# SCH_Light-Meter-Schematic_2025-04-22_1.net
KiCad netlist of a schematic drawn in EasyEDA
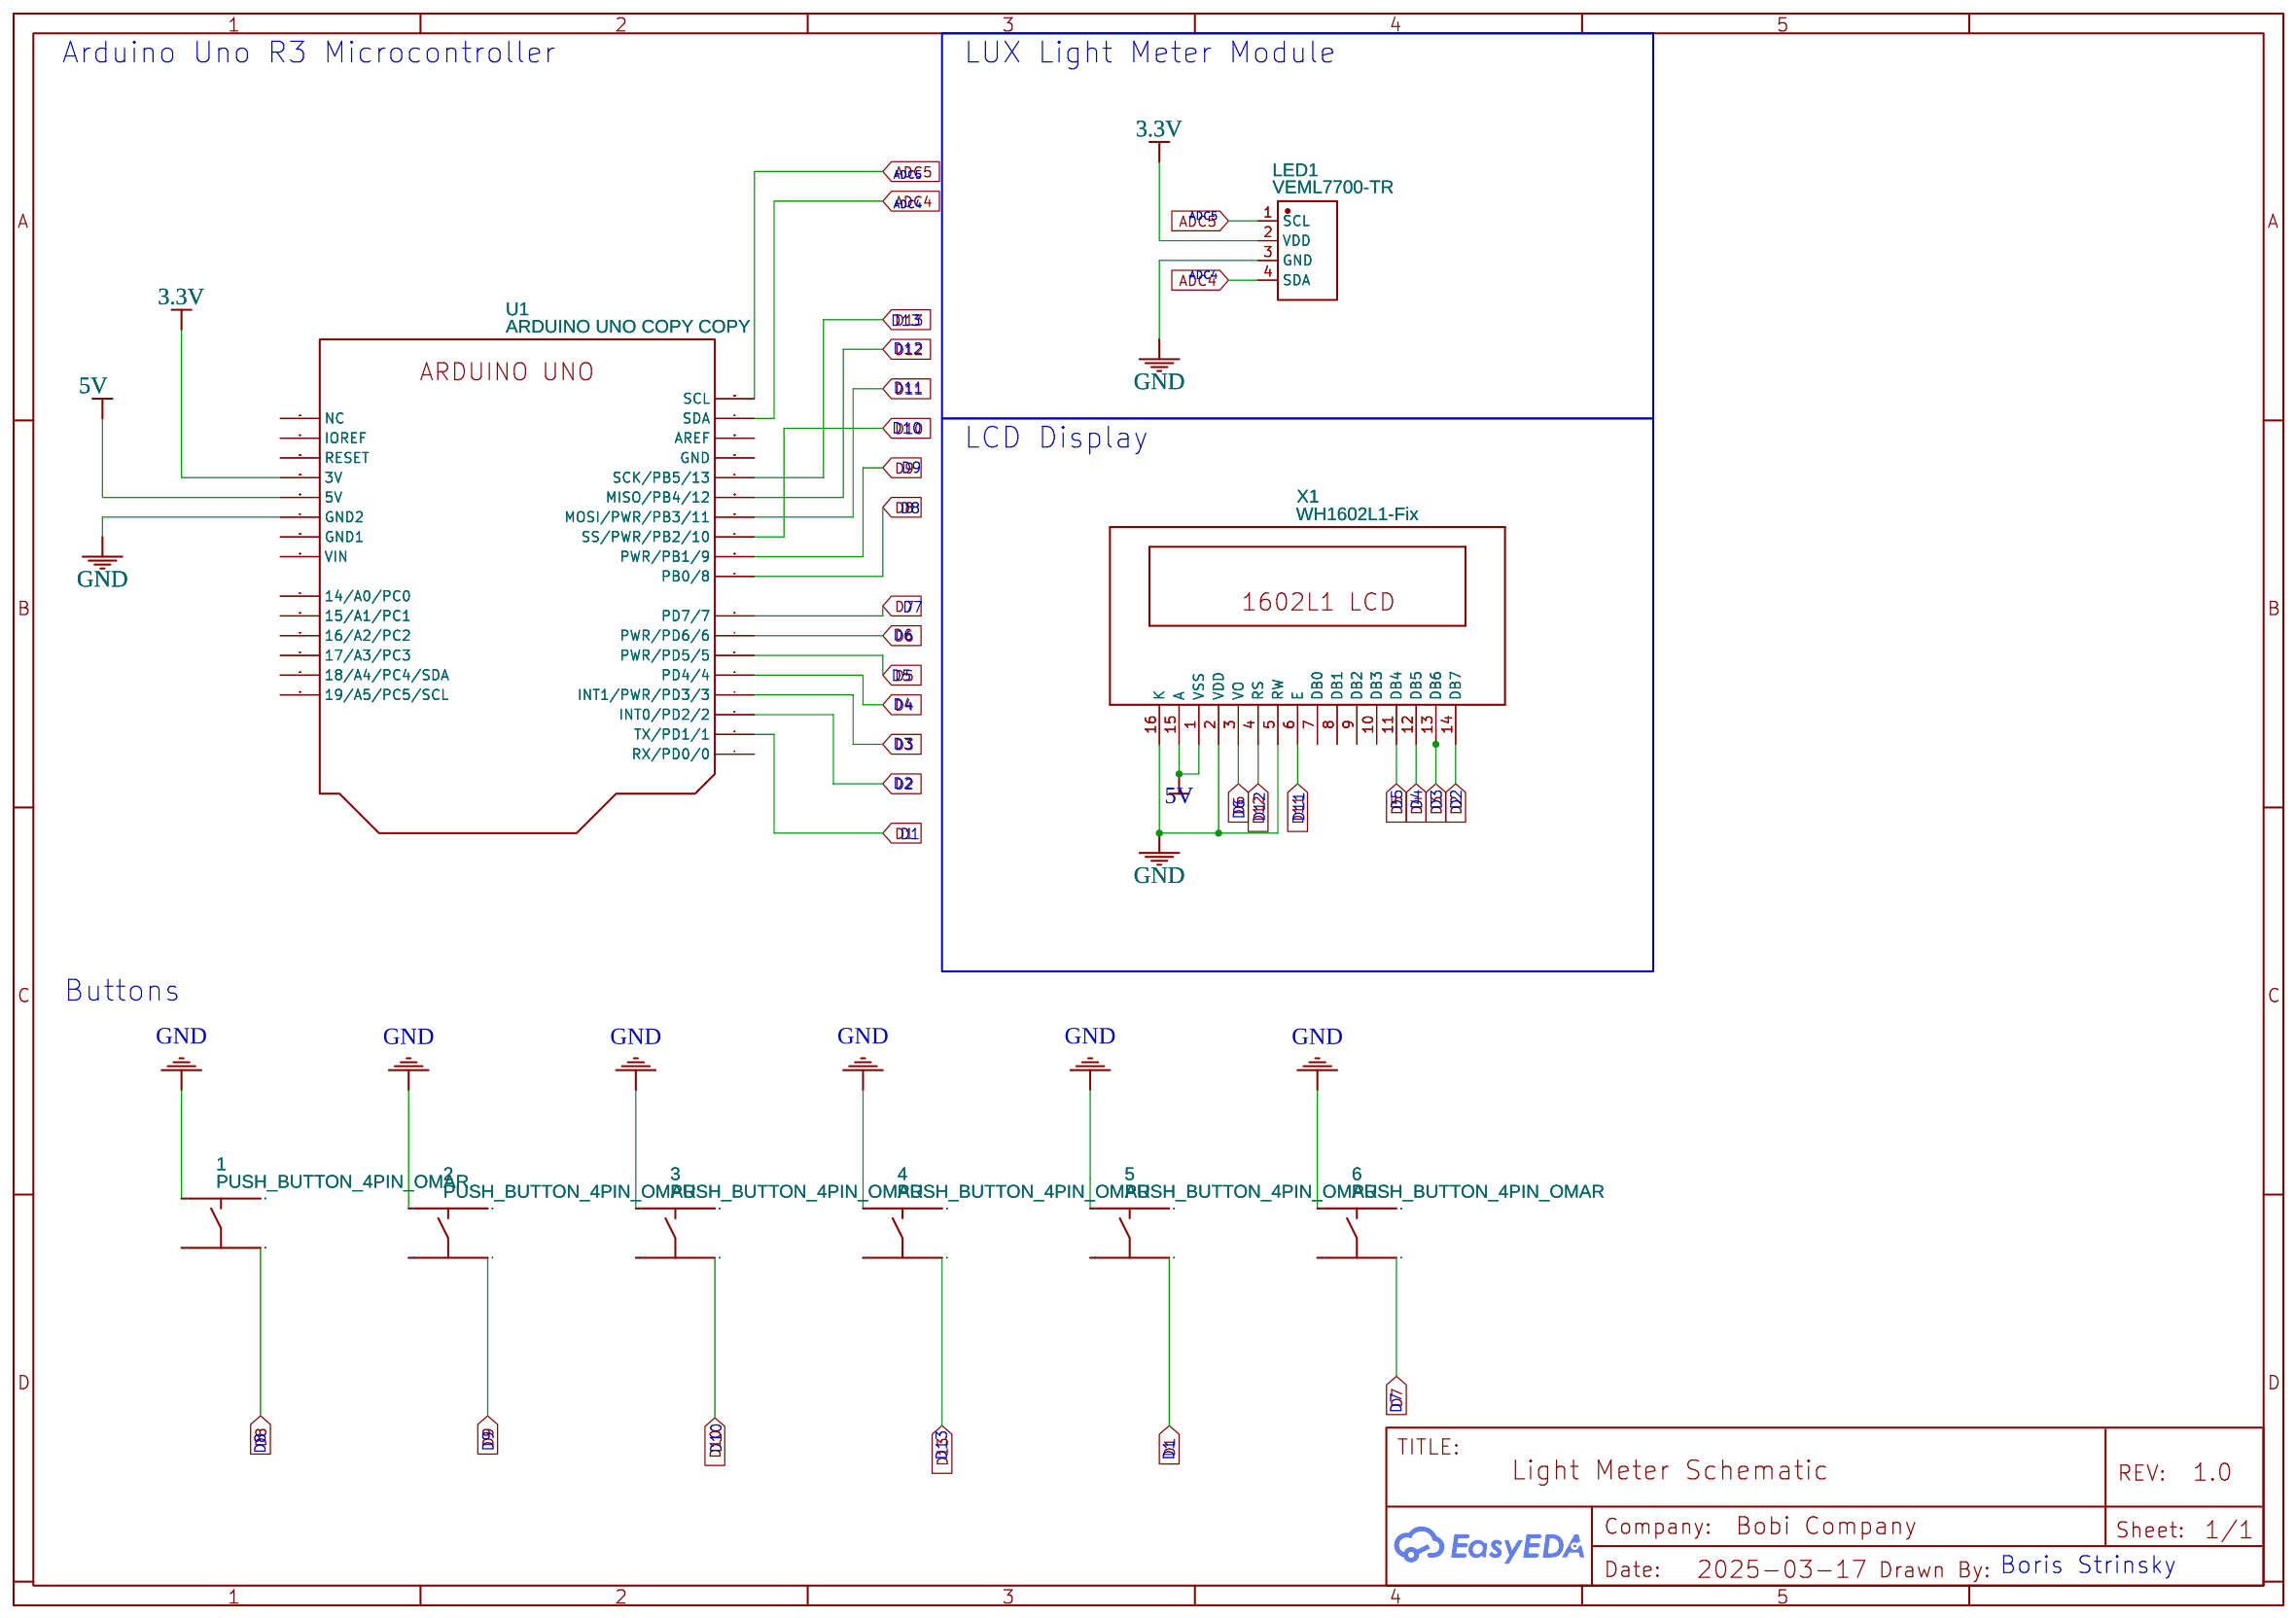
[diagram p0: schematic sheet]

(export (version "E")
  (design (tool "Eeschema 10.0.6"))
  (components
    (comp (ref "1") (value "PUSH_BUTTON_4PIN_OMAR") (libsource (lib "") (part "PUSH_BUTTON_4PIN_OMAR")))
    (comp (ref "2") (value "PUSH_BUTTON_4PIN_OMAR") (libsource (lib "") (part "PUSH_BUTTON_4PIN_OMAR")))
    (comp (ref "3") (value "PUSH_BUTTON_4PIN_OMAR") (libsource (lib "") (part "PUSH_BUTTON_4PIN_OMAR")))
    (comp (ref "4") (value "PUSH_BUTTON_4PIN_OMAR") (libsource (lib "") (part "PUSH_BUTTON_4PIN_OMAR")))
    (comp (ref "5") (value "PUSH_BUTTON_4PIN_OMAR") (libsource (lib "") (part "PUSH_BUTTON_4PIN_OMAR")))
    (comp (ref "6") (value "PUSH_BUTTON_4PIN_OMAR") (libsource (lib "") (part "PUSH_BUTTON_4PIN_OMAR")))
    (comp (ref "LED1")
      (value "VEML7700-TR")
      (fields (field (name "Manufacturer") "VISHAY(威世)"))
      (libsource (lib "") (part "VEML7700-TR"))
    )
    (comp (ref "U1") (value "ARDUINO UNO COPY COPY") (libsource (lib "") (part "ARDUINO UNO COPY COPY")))
    (comp (ref "X1") (value "WH1602L1-Fix") (libsource (lib "") (part "WH1602L1-Fix")))
  )
  (nets
    (net (code "1") (name "3.3V") (class "Default")
      (node (ref "LED1") (pin "2") (pinfunction "VDD_2") (pintype "unspecified"))
      (node (ref "U1") (pin "29") (pinfunction "3V_29") (pintype "passive"))
    )
    (net (code "2") (name "5V") (class "Default")
      (node (ref "U1") (pin "28") (pinfunction "5V_28") (pintype "passive"))
      (node (ref "X1") (pin "1") (pinfunction "VSS_1") (pintype "unspecified"))
      (node (ref "X1") (pin "15") (pinfunction "A_15") (pintype "input"))
    )
    (net (code "3") (name "ADC4") (class "Default")
      (node (ref "LED1") (pin "4") (pinfunction "SDA_4") (pintype "unspecified"))
      (node (ref "U1") (pin "17") (pinfunction "SDA_17") (pintype "unspecified"))
    )
    (net (code "4") (name "ADC5") (class "Default")
      (node (ref "LED1") (pin "1") (pinfunction "SCL_1") (pintype "unspecified"))
      (node (ref "U1") (pin "18") (pinfunction "SCL_18") (pintype "unspecified"))
    )
    (net (code "5") (name "D1") (class "Default")
      (node (ref "5") (pin "1") (pinfunction "1_1") (pintype "bidirectional"))
      (node (ref "U1") (pin "2") (pinfunction "TX/PD1/1_2") (pintype "unspecified"))
    )
    (net (code "6") (name "D2") (class "Default")
      (node (ref "U1") (pin "3") (pinfunction "INT0/PD2/2_3") (pintype "unspecified"))
      (node (ref "X1") (pin "14") (pinfunction "DB7_14") (pintype "unspecified"))
    )
    (net (code "7") (name "D3") (class "Default")
      (node (ref "U1") (pin "4") (pinfunction "INT1/PWR/PD3/3_4") (pintype "unspecified"))
      (node (ref "X1") (pin "13") (pinfunction "DB6_13") (pintype "unspecified"))
    )
    (net (code "8") (name "D4") (class "Default")
      (node (ref "U1") (pin "5") (pinfunction "PD4/4_5") (pintype "unspecified"))
      (node (ref "X1") (pin "12") (pinfunction "DB5_12") (pintype "unspecified"))
    )
    (net (code "9") (name "D5") (class "Default")
      (node (ref "U1") (pin "6") (pinfunction "PWR/PD5/5_6") (pintype "unspecified"))
      (node (ref "X1") (pin "11") (pinfunction "DB4_11") (pintype "unspecified"))
    )
    (net (code "10") (name "D6") (class "Default")
      (node (ref "U1") (pin "7") (pinfunction "PWR/PD6/6_7") (pintype "unspecified"))
      (node (ref "X1") (pin "3") (pinfunction "VO_3") (pintype "input"))
    )
    (net (code "11") (name "D7") (class "Default")
      (node (ref "6") (pin "1") (pinfunction "1_1") (pintype "bidirectional"))
      (node (ref "U1") (pin "8") (pinfunction "PD7/7_8") (pintype "unspecified"))
    )
    (net (code "12") (name "D8") (class "Default")
      (node (ref "1") (pin "1") (pinfunction "1_1") (pintype "bidirectional"))
      (node (ref "U1") (pin "9") (pinfunction "PB0/8_9") (pintype "unspecified"))
    )
    (net (code "13") (name "D9") (class "Default")
      (node (ref "2") (pin "1") (pinfunction "1_1") (pintype "bidirectional"))
      (node (ref "U1") (pin "10") (pinfunction "PWR/PB1/9_10") (pintype "unspecified"))
    )
    (net (code "14") (name "D10") (class "Default")
      (node (ref "3") (pin "1") (pinfunction "1_1") (pintype "bidirectional"))
      (node (ref "U1") (pin "11") (pinfunction "SS/PWR/PB2/10_11") (pintype "unspecified"))
    )
    (net (code "15") (name "D11") (class "Default")
      (node (ref "U1") (pin "12") (pinfunction "MOSI/PWR/PB3/11_12") (pintype "unspecified"))
      (node (ref "X1") (pin "6") (pinfunction "E_6") (pintype "input"))
    )
    (net (code "16") (name "D12") (class "Default")
      (node (ref "U1") (pin "13") (pinfunction "MISO/PB4/12_13") (pintype "unspecified"))
      (node (ref "X1") (pin "4") (pinfunction "RS_4") (pintype "input"))
    )
    (net (code "17") (name "D13") (class "Default")
      (node (ref "4") (pin "1") (pinfunction "1_1") (pintype "bidirectional"))
      (node (ref "U1") (pin "14") (pinfunction "SCK/PB5/13_14") (pintype "unspecified"))
    )
    (net (code "18") (name "GND") (class "Default")
      (node (ref "1") (pin "4") (pinfunction "4_4") (pintype "bidirectional"))
      (node (ref "2") (pin "4") (pinfunction "4_4") (pintype "bidirectional"))
      (node (ref "3") (pin "4") (pinfunction "4_4") (pintype "bidirectional"))
      (node (ref "4") (pin "4") (pinfunction "4_4") (pintype "bidirectional"))
      (node (ref "5") (pin "4") (pinfunction "4_4") (pintype "bidirectional"))
      (node (ref "6") (pin "4") (pinfunction "4_4") (pintype "bidirectional"))
      (node (ref "LED1") (pin "3") (pinfunction "GND_3") (pintype "unspecified"))
      (node (ref "U1") (pin "27") (pinfunction "GND2_27") (pintype "passive"))
      (node (ref "X1") (pin "16") (pinfunction "K_16") (pintype "input"))
      (node (ref "X1") (pin "2") (pinfunction "VDD_2") (pintype "unspecified"))
      (node (ref "X1") (pin "5") (pinfunction "RW_5") (pintype "input"))
    )
    (net (code "19") (name "unconnected-(1-Pad2)") (class "Default")
      (node (ref "1") (pin "2") (pinfunction "2_2") (pintype "bidirectional"))
    )
    (net (code "20") (name "unconnected-(1-Pad3)") (class "Default")
      (node (ref "1") (pin "3") (pinfunction "3_3") (pintype "bidirectional"))
    )
    (net (code "21") (name "unconnected-(2-Pad2)") (class "Default")
      (node (ref "2") (pin "2") (pinfunction "2_2") (pintype "bidirectional"))
    )
    (net (code "22") (name "unconnected-(2-Pad3)") (class "Default")
      (node (ref "2") (pin "3") (pinfunction "3_3") (pintype "bidirectional"))
    )
    (net (code "23") (name "unconnected-(3-Pad2)") (class "Default")
      (node (ref "3") (pin "2") (pinfunction "2_2") (pintype "bidirectional"))
    )
    (net (code "24") (name "unconnected-(3-Pad3)") (class "Default")
      (node (ref "3") (pin "3") (pinfunction "3_3") (pintype "bidirectional"))
    )
    (net (code "25") (name "unconnected-(4-Pad2)") (class "Default")
      (node (ref "4") (pin "2") (pinfunction "2_2") (pintype "bidirectional"))
    )
    (net (code "26") (name "unconnected-(4-Pad3)") (class "Default")
      (node (ref "4") (pin "3") (pinfunction "3_3") (pintype "bidirectional"))
    )
    (net (code "27") (name "unconnected-(5-Pad2)") (class "Default")
      (node (ref "5") (pin "2") (pinfunction "2_2") (pintype "bidirectional"))
    )
    (net (code "28") (name "unconnected-(5-Pad3)") (class "Default")
      (node (ref "5") (pin "3") (pinfunction "3_3") (pintype "bidirectional"))
    )
    (net (code "29") (name "unconnected-(6-Pad2)") (class "Default")
      (node (ref "6") (pin "2") (pinfunction "2_2") (pintype "bidirectional"))
    )
    (net (code "30") (name "unconnected-(6-Pad3)") (class "Default")
      (node (ref "6") (pin "3") (pinfunction "3_3") (pintype "bidirectional"))
    )
    (net (code "31") (name "unconnected-(U1-14{slash}A0{slash}PC0-Pad24)") (class "Default")
      (node (ref "U1") (pin "24") (pinfunction "14/A0/PC0_24") (pintype "unspecified"))
    )
    (net (code "32") (name "unconnected-(U1-15{slash}A1{slash}PC1-Pad23)") (class "Default")
      (node (ref "U1") (pin "23") (pinfunction "15/A1/PC1_23") (pintype "unspecified"))
    )
    (net (code "33") (name "unconnected-(U1-16{slash}A2{slash}PC2-Pad22)") (class "Default")
      (node (ref "U1") (pin "22") (pinfunction "16/A2/PC2_22") (pintype "unspecified"))
    )
    (net (code "34") (name "unconnected-(U1-17{slash}A3{slash}PC3-Pad21)") (class "Default")
      (node (ref "U1") (pin "21") (pinfunction "17/A3/PC3_21") (pintype "unspecified"))
    )
    (net (code "35") (name "unconnected-(U1-18{slash}A4{slash}PC4{slash}SDA-Pad20)") (class "Default")
      (node (ref "U1") (pin "20") (pinfunction "18/A4/PC4/SDA_20") (pintype "unspecified"))
    )
    (net (code "36") (name "unconnected-(U1-19{slash}A5{slash}PC5{slash}SCL-Pad19)") (class "Default")
      (node (ref "U1") (pin "19") (pinfunction "19/A5/PC5/SCL_19") (pintype "unspecified"))
    )
    (net (code "37") (name "unconnected-(U1-AREF-Pad16)") (class "Default")
      (node (ref "U1") (pin "16") (pinfunction "AREF_16") (pintype "unspecified"))
    )
    (net (code "38") (name "unconnected-(U1-GND-Pad15)") (class "Default")
      (node (ref "U1") (pin "15") (pinfunction "GND_15") (pintype "passive"))
    )
    (net (code "39") (name "unconnected-(U1-GND1-Pad26)") (class "Default")
      (node (ref "U1") (pin "26") (pinfunction "GND1_26") (pintype "passive"))
    )
    (net (code "40") (name "unconnected-(U1-IOREF-Pad31)") (class "Default")
      (node (ref "U1") (pin "31") (pinfunction "IOREF_31") (pintype "unspecified"))
    )
    (net (code "41") (name "unconnected-(U1-NC-Pad32)") (class "Default")
      (node (ref "U1") (pin "32") (pinfunction "NC_32") (pintype "unspecified"))
    )
    (net (code "42") (name "unconnected-(U1-RESET-Pad30)") (class "Default")
      (node (ref "U1") (pin "30") (pinfunction "RESET_30") (pintype "unspecified"))
    )
    (net (code "43") (name "unconnected-(U1-RX{slash}PD0{slash}0-Pad1)") (class "Default")
      (node (ref "U1") (pin "1") (pinfunction "RX/PD0/0_1") (pintype "unspecified"))
    )
    (net (code "44") (name "unconnected-(U1-VIN-Pad25)") (class "Default")
      (node (ref "U1") (pin "25") (pinfunction "VIN_25") (pintype "passive"))
    )
    (net (code "45") (name "unconnected-(X1-DB0-Pad7)") (class "Default")
      (node (ref "X1") (pin "7") (pinfunction "DB0_7") (pintype "unspecified"))
    )
    (net (code "46") (name "unconnected-(X1-DB1-Pad8)") (class "Default")
      (node (ref "X1") (pin "8") (pinfunction "DB1_8") (pintype "unspecified"))
    )
    (net (code "47") (name "unconnected-(X1-DB2-Pad9)") (class "Default")
      (node (ref "X1") (pin "9") (pinfunction "DB2_9") (pintype "unspecified"))
    )
    (net (code "48") (name "unconnected-(X1-DB3-Pad10)") (class "Default")
      (node (ref "X1") (pin "10") (pinfunction "DB3_10") (pintype "unspecified"))
    )
  )
)
